# ESP32.net
KiCad netlist of a schematic drawn in Altium Designer
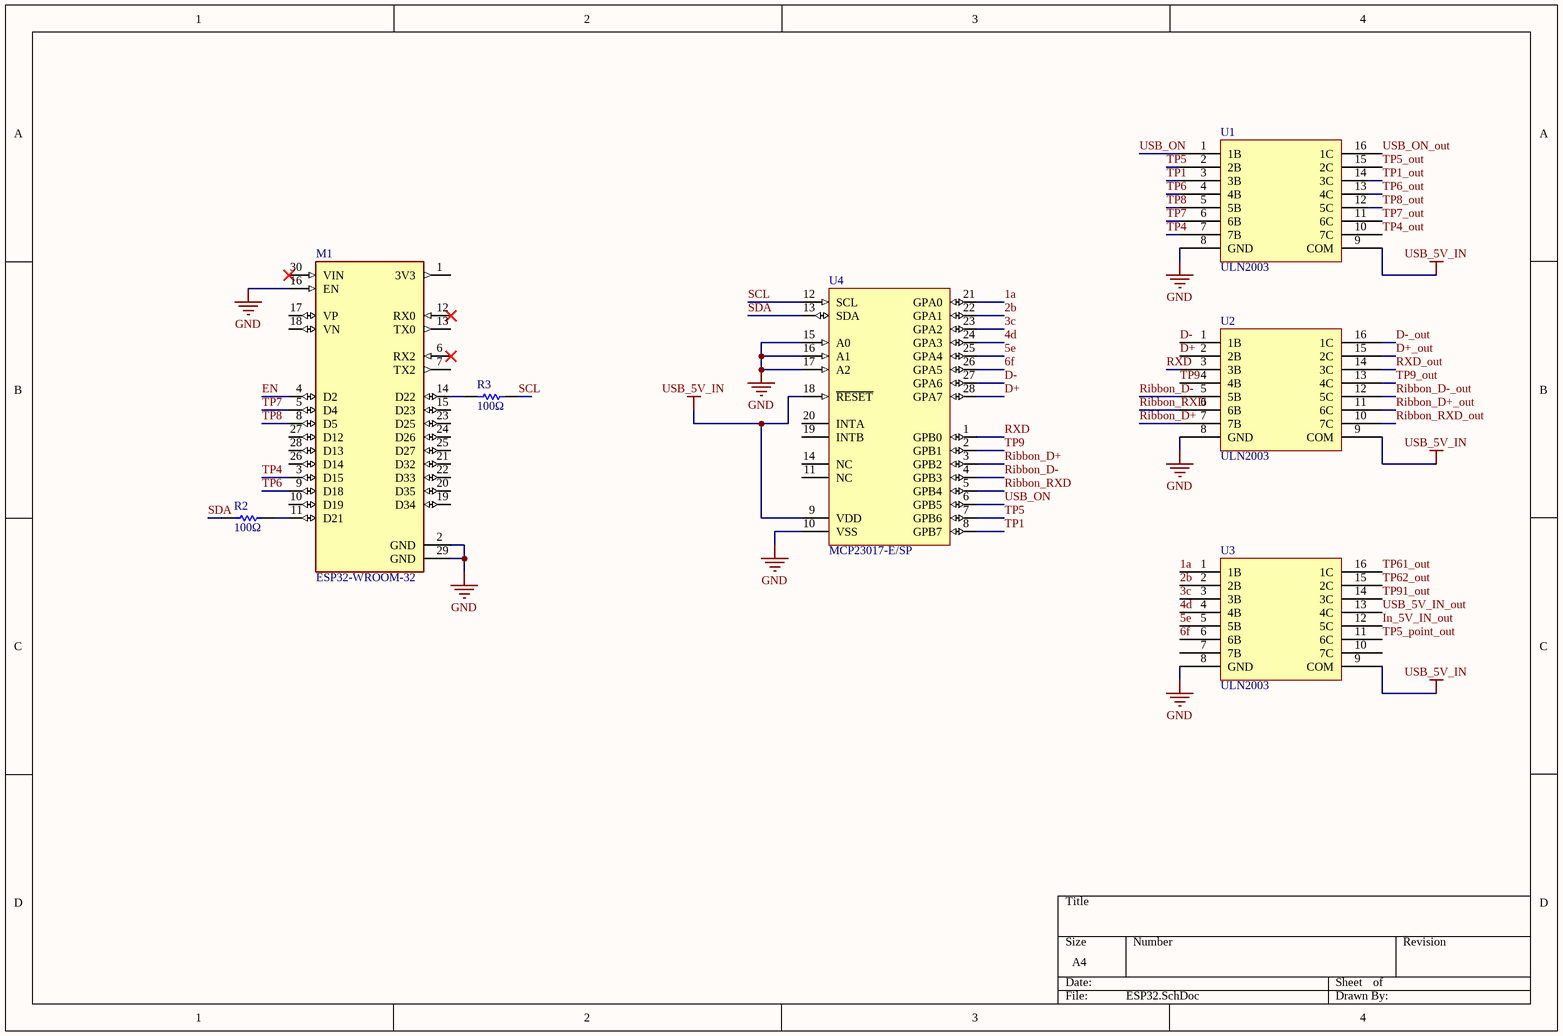
[diagram p0: ESP32.SchDoc]

(export (version "E")
  (design (tool "Eeschema 10.0.6"))
  (components
    (comp (ref "M1")
      (value "ESP32-WROOM-32")
      (footprint "ESP32-DEVKIT-V1")
      (libsource (lib "Modules") (part "ESP32-DEVKIT-V1"))
    )
    (comp (ref "R2")
      (value "100Ω")
      (footprint "RESC2013X60X40ML20T25")
      (description "Res Thin Film 0805 100 Ohm 0.1% 1/8W ±25ppm/°C Molded SMD SMD Punched Carrier T/R")
      (fields (field (name "MANUFACTURER") "Panasonic") (field (name "MFR. PART #") "ERA6AEB101V"))
      (libsource (lib "Altium Content Vault") (part "RES"))
    )
    (comp (ref "R3")
      (value "100Ω")
      (footprint "RESC2013X60X40ML20T25")
      (description "Res Thin Film 0805 100 Ohm 0.1% 1/8W ±25ppm/°C Molded SMD SMD Punched Carrier T/R")
      (fields (field (name "MANUFACTURER") "Panasonic") (field (name "MFR. PART #") "ERA6AEB101V"))
      (libsource (lib "Altium Content Vault") (part "RES"))
    )
    (comp (ref "U1")
      (value "ULN2003")
      (footprint "SOP127P600X175-16N")
      (description "SOP-16 Darlington Transistor Arrays ROHS")
      (fields (field (name "MANUFACTURER") "Changjiang Electronics Tech"))
      (libsource (lib "ULN2003") (part "Component_1"))
    )
    (comp (ref "U2")
      (value "ULN2003")
      (footprint "SOP127P600X175-16N")
      (fields (field (name "MANUFACTURER") "Changjiang Electronics Tech"))
      (libsource (lib "ULN2003") (part "Component_1"))
    )
    (comp (ref "U3")
      (value "ULN2003")
      (footprint "SOP127P600X175-16N")
      (fields (field (name "MANUFACTURER") "Changjiang Electronics Tech"))
      (libsource (lib "ULN2003") (part "Component_1"))
    )
    (comp (ref "U4")
      (value "MCP23017-E/SP")
      (footprint "SPDIP300-SP28")
      (description "16-Bit I/O Expander with Serial Interface, 28-Pin SPDIP, Extended Temperature")
      (fields (field (name "MANUFACTURER") "Microchip Tech"))
      (libsource (lib "Altium Content Vault") (part "PR-BUSIC-MCP23017-28"))
    )
  )
  (nets
    (net (code "1") (name "/1a") (class "Default")
      (node (ref "U3") (pin "1") (pinfunction "1B_1") (pintype "power_in"))
      (node (ref "U4") (pin "21") (pinfunction "GPA0_21") (pintype "bidirectional"))
    )
    (net (code "2") (name "/2b") (class "Default")
      (node (ref "U3") (pin "2") (pinfunction "2B_2") (pintype "power_in"))
      (node (ref "U4") (pin "22") (pinfunction "GPA1_22") (pintype "bidirectional"))
    )
    (net (code "3") (name "/3c") (class "Default")
      (node (ref "U3") (pin "3") (pinfunction "3B_3") (pintype "power_in"))
      (node (ref "U4") (pin "23") (pinfunction "GPA2_23") (pintype "bidirectional"))
    )
    (net (code "4") (name "/4d") (class "Default")
      (node (ref "U3") (pin "4") (pinfunction "4B_4") (pintype "power_in"))
      (node (ref "U4") (pin "24") (pinfunction "GPA3_24") (pintype "bidirectional"))
    )
    (net (code "5") (name "/5e") (class "Default")
      (node (ref "U3") (pin "5") (pinfunction "5B_5") (pintype "power_in"))
      (node (ref "U4") (pin "25") (pinfunction "GPA4_25") (pintype "bidirectional"))
    )
    (net (code "6") (name "/6f") (class "Default")
      (node (ref "U3") (pin "6") (pinfunction "6B_6") (pintype "power_in"))
      (node (ref "U4") (pin "26") (pinfunction "GPA5_26") (pintype "bidirectional"))
    )
    (net (code "7") (name "/D+") (class "Default")
      (node (ref "U2") (pin "2") (pinfunction "2B_2") (pintype "power_in"))
      (node (ref "U4") (pin "28") (pinfunction "GPA7_28") (pintype "bidirectional"))
    )
    (net (code "8") (name "/D+_out") (class "Default")
      (node (ref "U2") (pin "15") (pinfunction "2C_15") (pintype "power_in"))
    )
    (net (code "9") (name "/D-") (class "Default")
      (node (ref "U2") (pin "1") (pinfunction "1B_1") (pintype "power_in"))
      (node (ref "U4") (pin "27") (pinfunction "GPA6_27") (pintype "bidirectional"))
    )
    (net (code "10") (name "/D-_out") (class "Default")
      (node (ref "U2") (pin "16") (pinfunction "1C_16") (pintype "power_in"))
    )
    (net (code "11") (name "/EN") (class "Default")
      (node (ref "M1") (pin "4") (pinfunction "D2_4") (pintype "bidirectional"))
    )
    (net (code "12") (name "/In_5V_IN_out") (class "Default")
      (node (ref "U3") (pin "12") (pinfunction "5C_12") (pintype "power_in"))
    )
    (net (code "13") (name "/RXD") (class "Default")
      (node (ref "U2") (pin "3") (pinfunction "3B_3") (pintype "power_in"))
      (node (ref "U4") (pin "1") (pinfunction "GPB0_1") (pintype "bidirectional"))
    )
    (net (code "14") (name "/RXD_out") (class "Default")
      (node (ref "U2") (pin "14") (pinfunction "3C_14") (pintype "power_in"))
    )
    (net (code "15") (name "/Ribbon_D+") (class "Default")
      (node (ref "U2") (pin "7") (pinfunction "7B_7") (pintype "power_in"))
      (node (ref "U4") (pin "3") (pinfunction "GPB2_3") (pintype "bidirectional"))
    )
    (net (code "16") (name "/Ribbon_D+_out") (class "Default")
      (node (ref "U2") (pin "11") (pinfunction "6C_11") (pintype "power_in"))
    )
    (net (code "17") (name "/Ribbon_D-") (class "Default")
      (node (ref "U2") (pin "5") (pinfunction "5B_5") (pintype "power_in"))
      (node (ref "U4") (pin "4") (pinfunction "GPB3_4") (pintype "bidirectional"))
    )
    (net (code "18") (name "/Ribbon_D-_out") (class "Default")
      (node (ref "U2") (pin "12") (pinfunction "5C_12") (pintype "power_in"))
    )
    (net (code "19") (name "/Ribbon_RXD") (class "Default")
      (node (ref "U2") (pin "6") (pinfunction "6B_6") (pintype "power_in"))
      (node (ref "U4") (pin "5") (pinfunction "GPB4_5") (pintype "bidirectional"))
    )
    (net (code "20") (name "/Ribbon_RXD_out") (class "Default")
      (node (ref "U2") (pin "10") (pinfunction "7C_10") (pintype "power_in"))
    )
    (net (code "21") (name "/SCL") (class "Default")
      (node (ref "R3") (pin "2") (pinfunction "2_2") (pintype "passive"))
      (node (ref "U4") (pin "12") (pinfunction "SCL_12") (pintype "input"))
    )
    (net (code "22") (name "/SDA") (class "Default")
      (node (ref "R2") (pin "1") (pinfunction "1_1") (pintype "passive"))
      (node (ref "U4") (pin "13") (pinfunction "SDA_13") (pintype "bidirectional"))
    )
    (net (code "23") (name "/TP1") (class "Default")
      (node (ref "U1") (pin "3") (pinfunction "3B_3") (pintype "power_in"))
      (node (ref "U4") (pin "8") (pinfunction "GPB7_8") (pintype "bidirectional"))
    )
    (net (code "24") (name "/TP1_out") (class "Default")
      (node (ref "U1") (pin "14") (pinfunction "3C_14") (pintype "power_in"))
    )
    (net (code "25") (name "/TP4") (class "Default")
      (node (ref "M1") (pin "3") (pinfunction "D15_3") (pintype "bidirectional"))
      (node (ref "U1") (pin "7") (pinfunction "7B_7") (pintype "power_in"))
    )
    (net (code "26") (name "/TP4_out") (class "Default")
      (node (ref "U1") (pin "10") (pinfunction "7C_10") (pintype "power_in"))
    )
    (net (code "27") (name "/TP5") (class "Default")
      (node (ref "U1") (pin "2") (pinfunction "2B_2") (pintype "power_in"))
      (node (ref "U4") (pin "7") (pinfunction "GPB6_7") (pintype "bidirectional"))
    )
    (net (code "28") (name "/TP5_out") (class "Default")
      (node (ref "U1") (pin "15") (pinfunction "2C_15") (pintype "power_in"))
    )
    (net (code "29") (name "/TP5_point_out") (class "Default")
      (node (ref "U3") (pin "11") (pinfunction "6C_11") (pintype "power_in"))
    )
    (net (code "30") (name "/TP6") (class "Default")
      (node (ref "M1") (pin "9") (pinfunction "D18_9") (pintype "bidirectional"))
      (node (ref "U1") (pin "4") (pinfunction "4B_4") (pintype "power_in"))
    )
    (net (code "31") (name "/TP6_out") (class "Default")
      (node (ref "U1") (pin "13") (pinfunction "4C_13") (pintype "power_in"))
    )
    (net (code "32") (name "/TP7") (class "Default")
      (node (ref "M1") (pin "5") (pinfunction "D4_5") (pintype "bidirectional"))
      (node (ref "U1") (pin "6") (pinfunction "6B_6") (pintype "power_in"))
    )
    (net (code "33") (name "/TP7_out") (class "Default")
      (node (ref "U1") (pin "11") (pinfunction "6C_11") (pintype "power_in"))
    )
    (net (code "34") (name "/TP8") (class "Default")
      (node (ref "M1") (pin "8") (pinfunction "D5_8") (pintype "bidirectional"))
      (node (ref "U1") (pin "5") (pinfunction "5B_5") (pintype "power_in"))
    )
    (net (code "35") (name "/TP8_out") (class "Default")
      (node (ref "U1") (pin "12") (pinfunction "5C_12") (pintype "power_in"))
    )
    (net (code "36") (name "/TP9") (class "Default")
      (node (ref "U2") (pin "4") (pinfunction "4B_4") (pintype "power_in"))
      (node (ref "U4") (pin "2") (pinfunction "GPB1_2") (pintype "bidirectional"))
    )
    (net (code "37") (name "/TP9_out") (class "Default")
      (node (ref "U2") (pin "13") (pinfunction "4C_13") (pintype "power_in"))
    )
    (net (code "38") (name "/TP61_out") (class "Default")
      (node (ref "U3") (pin "16") (pinfunction "1C_16") (pintype "power_in"))
    )
    (net (code "39") (name "/TP62_out") (class "Default")
      (node (ref "U3") (pin "15") (pinfunction "2C_15") (pintype "power_in"))
    )
    (net (code "40") (name "/TP91_out") (class "Default")
      (node (ref "U3") (pin "14") (pinfunction "3C_14") (pintype "power_in"))
    )
    (net (code "41") (name "/USB_5V_IN_out") (class "Default")
      (node (ref "U3") (pin "13") (pinfunction "4C_13") (pintype "power_in"))
    )
    (net (code "42") (name "/USB_ON") (class "Default")
      (node (ref "U1") (pin "1") (pinfunction "1B_1") (pintype "power_in"))
      (node (ref "U4") (pin "6") (pinfunction "GPB5_6") (pintype "bidirectional"))
    )
    (net (code "43") (name "/USB_ON_out") (class "Default")
      (node (ref "U1") (pin "16") (pinfunction "1C_16") (pintype "power_in"))
    )
    (net (code "44") (name "GND") (class "Default")
      (node (ref "M1") (pin "16") (pinfunction "EN_16") (pintype "input"))
      (node (ref "M1") (pin "2") (pinfunction "GND_2") (pintype "power_in"))
      (node (ref "M1") (pin "29") (pinfunction "GND_29") (pintype "power_in"))
      (node (ref "U1") (pin "8") (pinfunction "GND_8") (pintype "power_in"))
      (node (ref "U2") (pin "8") (pinfunction "GND_8") (pintype "power_in"))
      (node (ref "U3") (pin "8") (pinfunction "GND_8") (pintype "power_in"))
      (node (ref "U4") (pin "10") (pinfunction "VSS_10") (pintype "power_in"))
      (node (ref "U4") (pin "15") (pinfunction "A0_15") (pintype "input"))
      (node (ref "U4") (pin "16") (pinfunction "A1_16") (pintype "input"))
      (node (ref "U4") (pin "17") (pinfunction "A2_17") (pintype "input"))
    )
    (net (code "45") (name "Net-(M1-D21)") (class "Default")
      (node (ref "M1") (pin "11") (pinfunction "D21_11") (pintype "bidirectional"))
      (node (ref "R2") (pin "2") (pinfunction "2_2") (pintype "passive"))
    )
    (net (code "46") (name "Net-(M1-D22)") (class "Default")
      (node (ref "M1") (pin "14") (pinfunction "D22_14") (pintype "bidirectional"))
      (node (ref "R3") (pin "1") (pinfunction "1_1") (pintype "passive"))
    )
    (net (code "47") (name "USB_5V_IN") (class "Default")
      (node (ref "U1") (pin "9") (pinfunction "COM_9") (pintype "power_in"))
      (node (ref "U2") (pin "9") (pinfunction "COM_9") (pintype "power_in"))
      (node (ref "U3") (pin "9") (pinfunction "COM_9") (pintype "power_in"))
      (node (ref "U4") (pin "18") (pinfunction "~{RESET}_18") (pintype "input"))
      (node (ref "U4") (pin "9") (pinfunction "VDD_9") (pintype "power_in"))
    )
    (net (code "48") (name "unconnected-(M1-3V3-Pad1)") (class "Default")
      (node (ref "M1") (pin "1") (pinfunction "3V3_1") (pintype "output"))
    )
    (net (code "49") (name "unconnected-(M1-D12-Pad27)") (class "Default")
      (node (ref "M1") (pin "27") (pinfunction "D12_27") (pintype "bidirectional"))
    )
    (net (code "50") (name "unconnected-(M1-D13-Pad28)") (class "Default")
      (node (ref "M1") (pin "28") (pinfunction "D13_28") (pintype "bidirectional"))
    )
    (net (code "51") (name "unconnected-(M1-D14-Pad26)") (class "Default")
      (node (ref "M1") (pin "26") (pinfunction "D14_26") (pintype "bidirectional"))
    )
    (net (code "52") (name "unconnected-(M1-D19-Pad10)") (class "Default")
      (node (ref "M1") (pin "10") (pinfunction "D19_10") (pintype "bidirectional"))
    )
    (net (code "53") (name "unconnected-(M1-D23-Pad15)") (class "Default")
      (node (ref "M1") (pin "15") (pinfunction "D23_15") (pintype "bidirectional"))
    )
    (net (code "54") (name "unconnected-(M1-D25-Pad23)") (class "Default")
      (node (ref "M1") (pin "23") (pinfunction "D25_23") (pintype "bidirectional"))
    )
    (net (code "55") (name "unconnected-(M1-D26-Pad24)") (class "Default")
      (node (ref "M1") (pin "24") (pinfunction "D26_24") (pintype "bidirectional"))
    )
    (net (code "56") (name "unconnected-(M1-D27-Pad25)") (class "Default")
      (node (ref "M1") (pin "25") (pinfunction "D27_25") (pintype "bidirectional"))
    )
    (net (code "57") (name "unconnected-(M1-D32-Pad21)") (class "Default")
      (node (ref "M1") (pin "21") (pinfunction "D32_21") (pintype "bidirectional"))
    )
    (net (code "58") (name "unconnected-(M1-D33-Pad22)") (class "Default")
      (node (ref "M1") (pin "22") (pinfunction "D33_22") (pintype "bidirectional"))
    )
    (net (code "59") (name "unconnected-(M1-D34-Pad19)") (class "Default")
      (node (ref "M1") (pin "19") (pinfunction "D34_19") (pintype "bidirectional"))
    )
    (net (code "60") (name "unconnected-(M1-D35-Pad20)") (class "Default")
      (node (ref "M1") (pin "20") (pinfunction "D35_20") (pintype "bidirectional"))
    )
    (net (code "61") (name "unconnected-(M1-RX0-Pad12)") (class "Default")
      (node (ref "M1") (pin "12") (pinfunction "RX0_12") (pintype "input+no_connect"))
    )
    (net (code "62") (name "unconnected-(M1-RX2-Pad6)") (class "Default")
      (node (ref "M1") (pin "6") (pinfunction "RX2_6") (pintype "input+no_connect"))
    )
    (net (code "63") (name "unconnected-(M1-TX0-Pad13)") (class "Default")
      (node (ref "M1") (pin "13") (pinfunction "TX0_13") (pintype "output"))
    )
    (net (code "64") (name "unconnected-(M1-TX2-Pad7)") (class "Default")
      (node (ref "M1") (pin "7") (pinfunction "TX2_7") (pintype "output"))
    )
    (net (code "65") (name "unconnected-(M1-VIN-Pad30)") (class "Default")
      (node (ref "M1") (pin "30") (pinfunction "VIN_30") (pintype "input+no_connect"))
    )
    (net (code "66") (name "unconnected-(M1-VN-Pad18)") (class "Default")
      (node (ref "M1") (pin "18") (pinfunction "VN_18") (pintype "bidirectional"))
    )
    (net (code "67") (name "unconnected-(M1-VP-Pad17)") (class "Default")
      (node (ref "M1") (pin "17") (pinfunction "VP_17") (pintype "bidirectional"))
    )
    (net (code "68") (name "unconnected-(U3-7B-Pad7)") (class "Default")
      (node (ref "U3") (pin "7") (pinfunction "7B_7") (pintype "power_in"))
    )
    (net (code "69") (name "unconnected-(U3-7C-Pad10)") (class "Default")
      (node (ref "U3") (pin "10") (pinfunction "7C_10") (pintype "power_in"))
    )
    (net (code "70") (name "unconnected-(U4-INTA-Pad20)") (class "Default")
      (node (ref "U4") (pin "20") (pinfunction "INTA_20") (pintype "open_collector"))
    )
    (net (code "71") (name "unconnected-(U4-INTB-Pad19)") (class "Default")
      (node (ref "U4") (pin "19") (pinfunction "INTB_19") (pintype "open_collector"))
    )
    (net (code "72") (name "unconnected-(U4-NC-Pad11)") (class "Default")
      (node (ref "U4") (pin "11") (pinfunction "NC_11") (pintype "passive"))
    )
    (net (code "73") (name "unconnected-(U4-NC-Pad14)") (class "Default")
      (node (ref "U4") (pin "14") (pinfunction "NC_14") (pintype "passive"))
    )
  )
)
